# SENSOR.net
KiCad netlist of a schematic drawn in Altium Designer
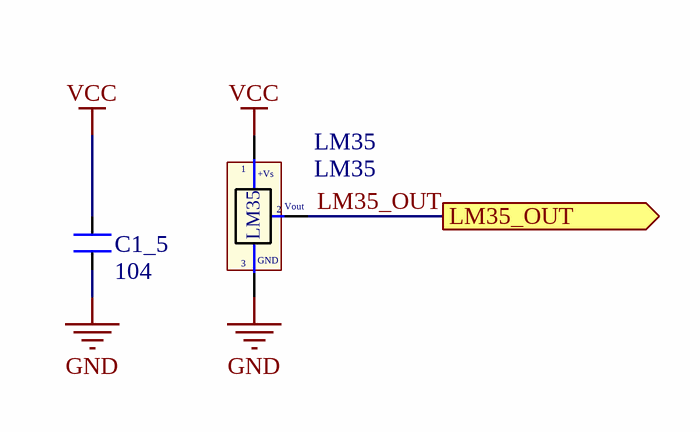
[diagram p0: SENSOR.SchDoc]

(export (version "E")
  (design (tool "Eeschema 10.0.6"))
  (components
    (comp (ref "C1_5") (value "104") (footprint "CN-SMD-0805") (libsource (lib "Altium Library") (part "CN")))
    (comp (ref "LM35")
      (value "LM35")
      (footprint "TO92-123")
      (description "Teminal")
      (libsource (lib "Altium Library") (part "LM35"))
    )
  )
  (nets
    (net (code "1") (name "/LM35_OUT") (class "Default")
      (node (ref "LM35") (pin "2") (pinfunction "Vout_2") (pintype "passive"))
    )
    (net (code "2") (name "GND") (class "Default")
      (node (ref "C1_5") (pin "1") (pinfunction "1_1") (pintype "passive"))
      (node (ref "LM35") (pin "3") (pinfunction "-_3") (pintype "passive"))
    )
    (net (code "3") (name "VCC") (class "Default")
      (node (ref "C1_5") (pin "2") (pinfunction "2_2") (pintype "passive"))
      (node (ref "LM35") (pin "1") (pinfunction "+Vs_1") (pintype "passive"))
    )
  )
)
